# UPV.net
KiCad netlist of a schematic drawn in Altium Designer
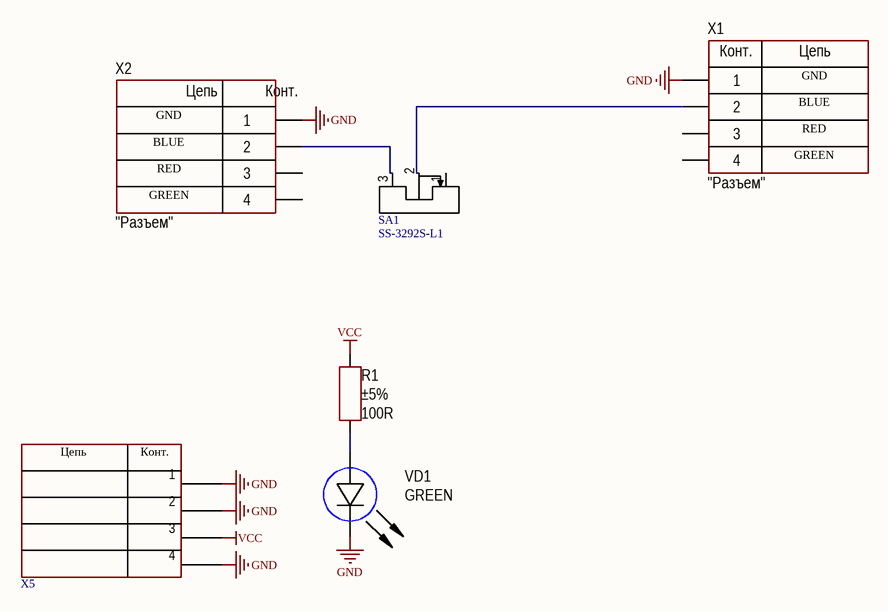
[diagram p0: UPV.SchDoc]

(export (version "E")
  (design (tool "Eeschema 10.0.6"))
  (components
    (comp (ref "R1")
      (value "100R")
      (footprint "RES: 0603")
      (fields
        (field (name "MANUFACTURER") "Yageo")
        (field (name "PARTNUMBER") "RC0603JR-07100RL")
        (field (name "VALUEMANUFACTURERPARTNUMBER") "Resistor film, 100R, ±5%, 0603, 0.1W, -55...+125°C")
        (field (name "TOLERANCE") "±5%")
      )
      (libsource (lib "Resistor") (part "Resistor_0603"))
    )
    (comp (ref "SA1")
      (value "SS-3292S-L1")
      (footprint "SS-3292S-L1")
      (libsource (lib "switch") (part "SS-3292S-L1"))
    )
    (comp (ref "VD1")
      (value "~")
      (footprint "LED: 0805G")
      (fields
        (field (name "VALUEMANUFACTURERPARTNUMBER") "LED, *, *, *, -55...+150°C")
        (field (name "COLOR") "GREEN")
      )
      (libsource (lib "Diode") (part "LED_single"))
    )
    (comp (ref "X1")
      (value "~")
      (footprint "4PLS RIGHT ANGLE 2")
      (fields
        (field (name "MANUFACTURER") "Connfly")
        (field (name "VALUEMANUFACTURERPARTNUMBER") "Connector, 4pin, 2.54mm, 500VAC, 3A")
        (field (name "PARTNUMBER") "PLS-4")
        (field (name "COMMENTTEXT") "\"Разъем\"")
      )
      (libsource (lib "Connector") (part "PLS-4"))
    )
    (comp (ref "X2")
      (value "~")
      (footprint "CON: PBS-4 R")
      (fields
        (field (name "MANUFACTURER") "Connfly")
        (field (name "VALUEMANUFACTURERPARTNUMBER") "Connector, 4pin, 2.54mm, 500VAC, 3A")
        (field (name "PARTNUMBER") "PBS-4")
        (field (name "COMMENTTEXT") "\"Разъем\"")
      )
      (libsource (lib "Connector") (part "PBS-4"))
    )
    (comp (ref "X5")
      (value "PBS-4 cut")
      (footprint "PBS-4 CUT")
      (libsource (lib "conect") (part "PBS-4 cut"))
    )
  )
  (nets
    (net (code "1") (name "GND") (class "Default")
      (node (ref "VD1") (pin "2") (pinfunction "C_2") (pintype "passive"))
      (node (ref "X1") (pin "1") (pinfunction "1_1") (pintype "passive"))
      (node (ref "X2") (pin "1") (pinfunction "1_1") (pintype "passive"))
      (node (ref "X5") (pin "1") (pinfunction "1_1") (pintype "passive"))
      (node (ref "X5") (pin "2") (pinfunction "2_2") (pintype "passive"))
      (node (ref "X5") (pin "4") (pinfunction "4_4") (pintype "passive"))
    )
    (net (code "2") (name "Net-(SA1-Pad2)") (class "Default")
      (node (ref "SA1") (pin "2") (pinfunction "2_2") (pintype "passive"))
      (node (ref "X1") (pin "2") (pinfunction "2_2") (pintype "passive"))
    )
    (net (code "3") (name "Net-(SA1-Pad3)") (class "Default")
      (node (ref "SA1") (pin "3") (pinfunction "3_3") (pintype "passive"))
      (node (ref "X2") (pin "2") (pinfunction "2_2") (pintype "passive"))
    )
    (net (code "4") (name "Net-(VD1-A)") (class "Default")
      (node (ref "R1") (pin "1") (pinfunction "1_1") (pintype "passive"))
      (node (ref "VD1") (pin "1") (pinfunction "A_1") (pintype "passive"))
    )
    (net (code "5") (name "VCC") (class "Default")
      (node (ref "R1") (pin "2") (pinfunction "2_2") (pintype "passive"))
      (node (ref "X5") (pin "3") (pinfunction "3_3") (pintype "passive"))
    )
    (net (code "6") (name "unconnected-(SA1-Pad1)") (class "Default")
      (node (ref "SA1") (pin "1") (pinfunction "1_1") (pintype "passive"))
    )
    (net (code "7") (name "unconnected-(X1-Pad3)") (class "Default")
      (node (ref "X1") (pin "3") (pinfunction "3_3") (pintype "power_in"))
    )
    (net (code "8") (name "unconnected-(X1-Pad4)") (class "Default")
      (node (ref "X1") (pin "4") (pinfunction "4_4") (pintype "power_in"))
    )
    (net (code "9") (name "unconnected-(X2-Pad3)") (class "Default")
      (node (ref "X2") (pin "3") (pinfunction "3_3") (pintype "power_in"))
    )
    (net (code "10") (name "unconnected-(X2-Pad4)") (class "Default")
      (node (ref "X2") (pin "4") (pinfunction "4_4") (pintype "power_in"))
    )
  )
)
